# pcb1_24V.net
KiCad netlist of a schematic drawn in EAGLE
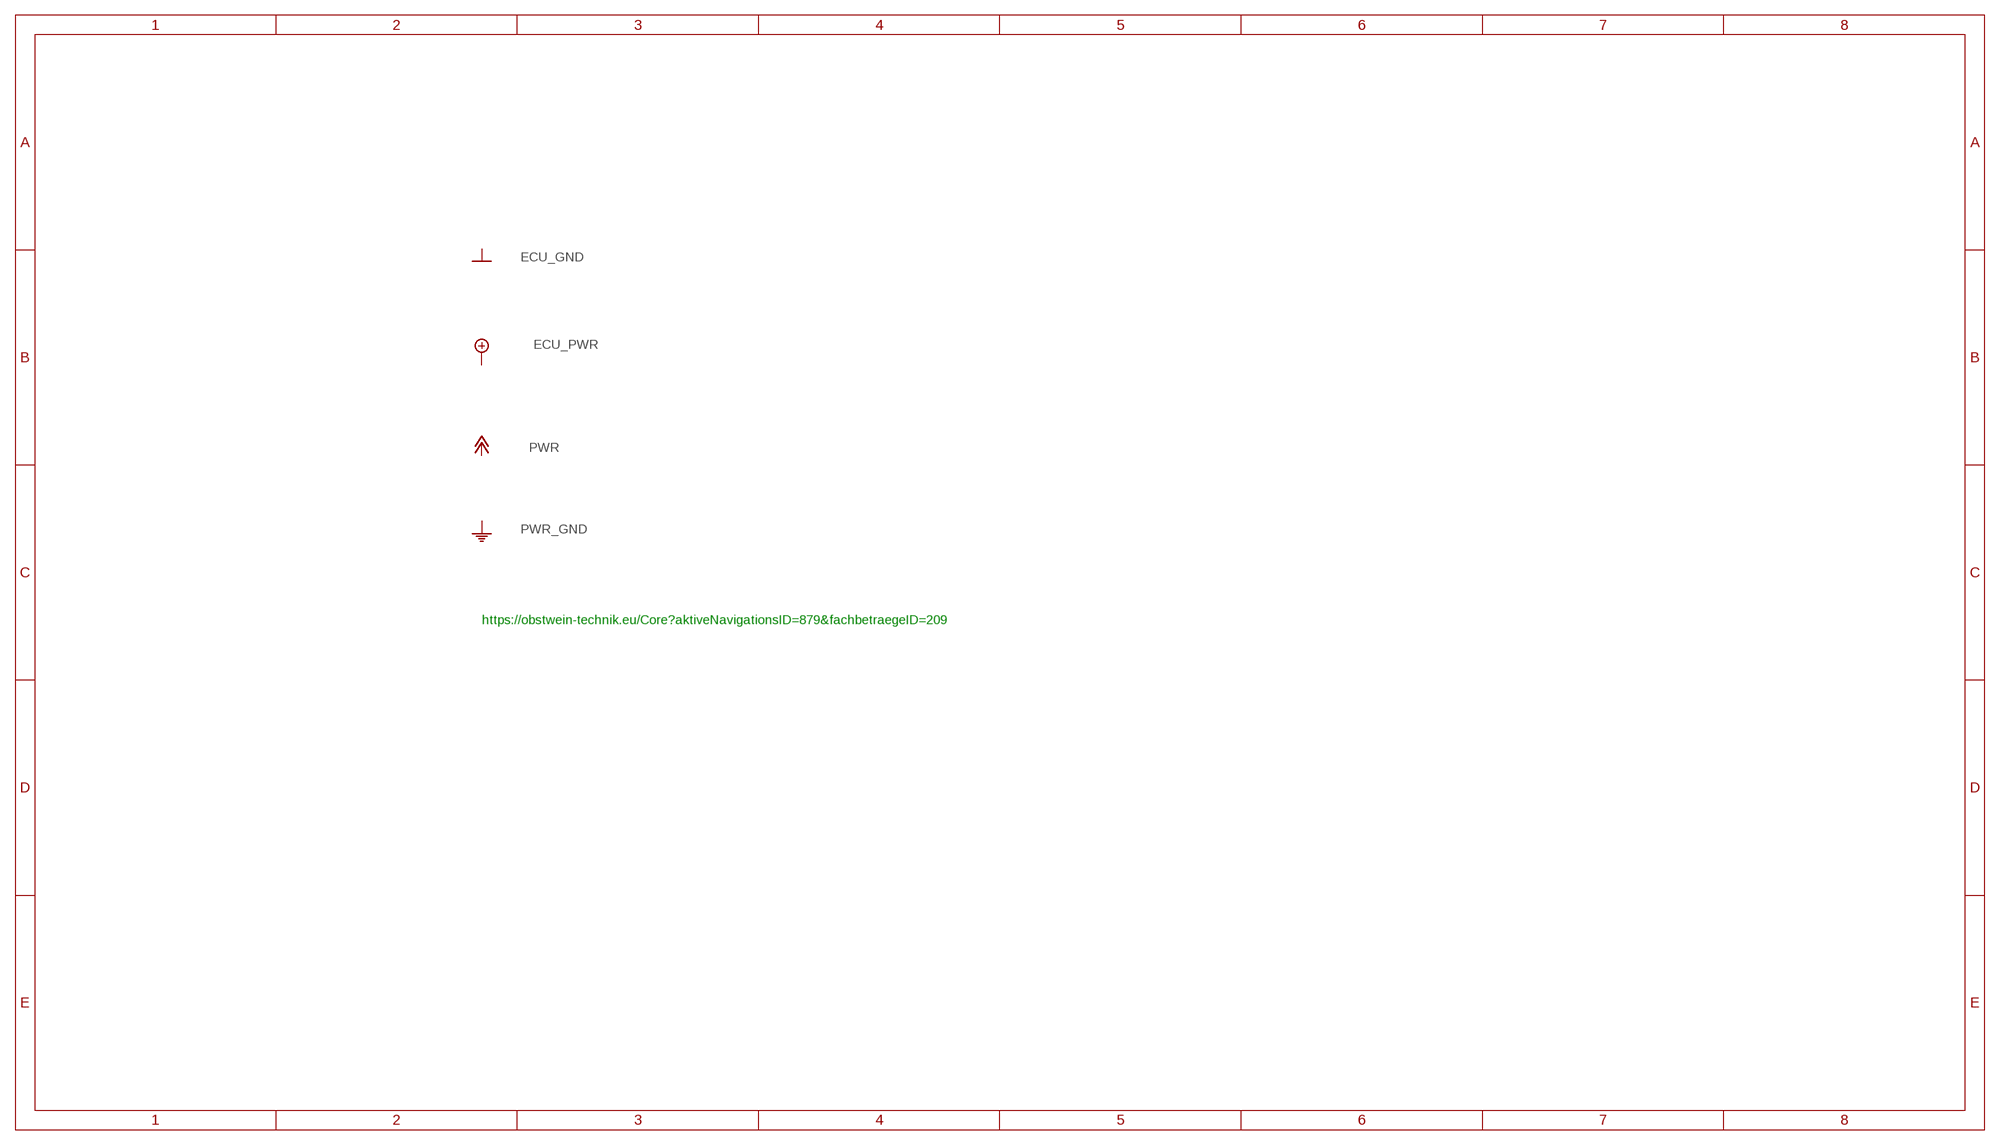
[diagram p0: schematic, sheet 1]
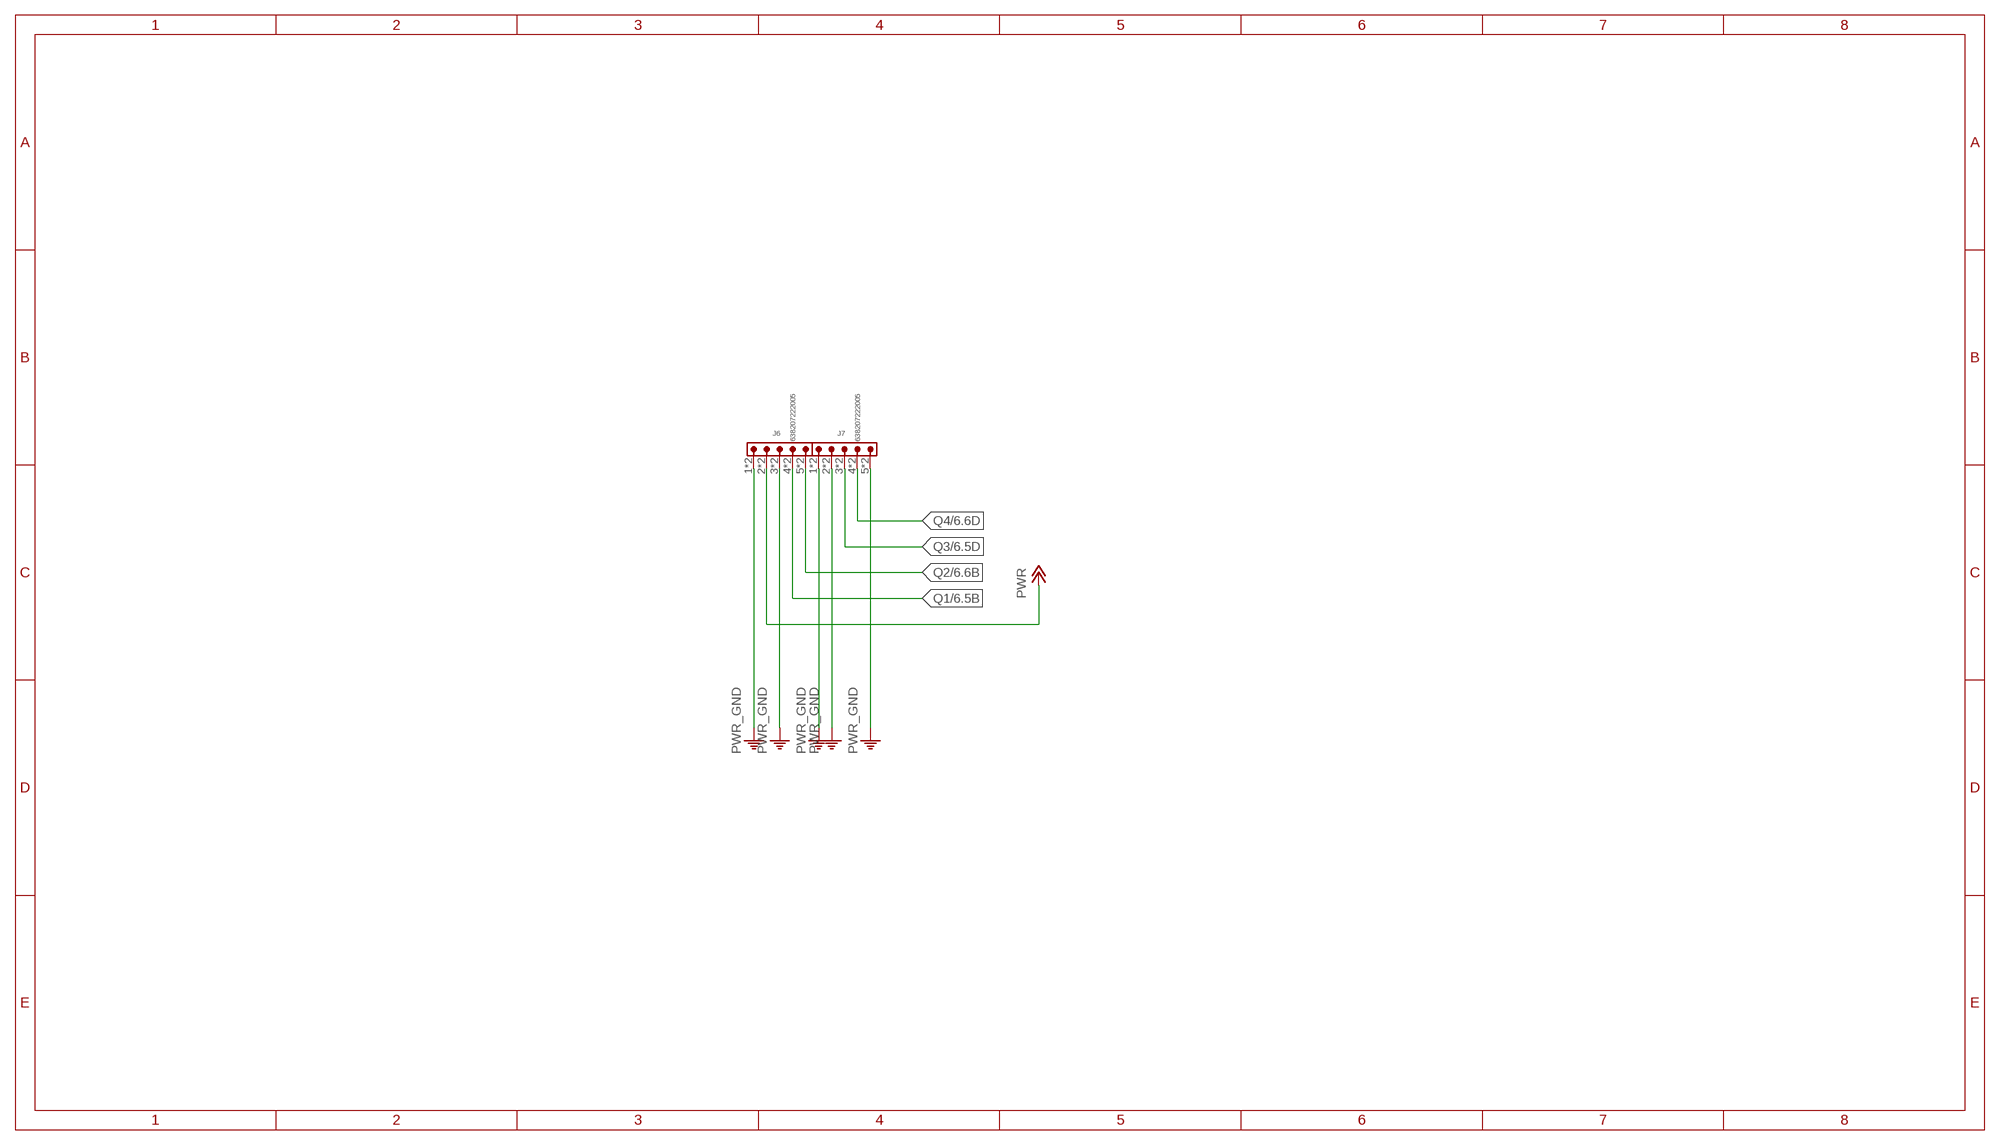
[diagram p1: schematic, sheet 2]
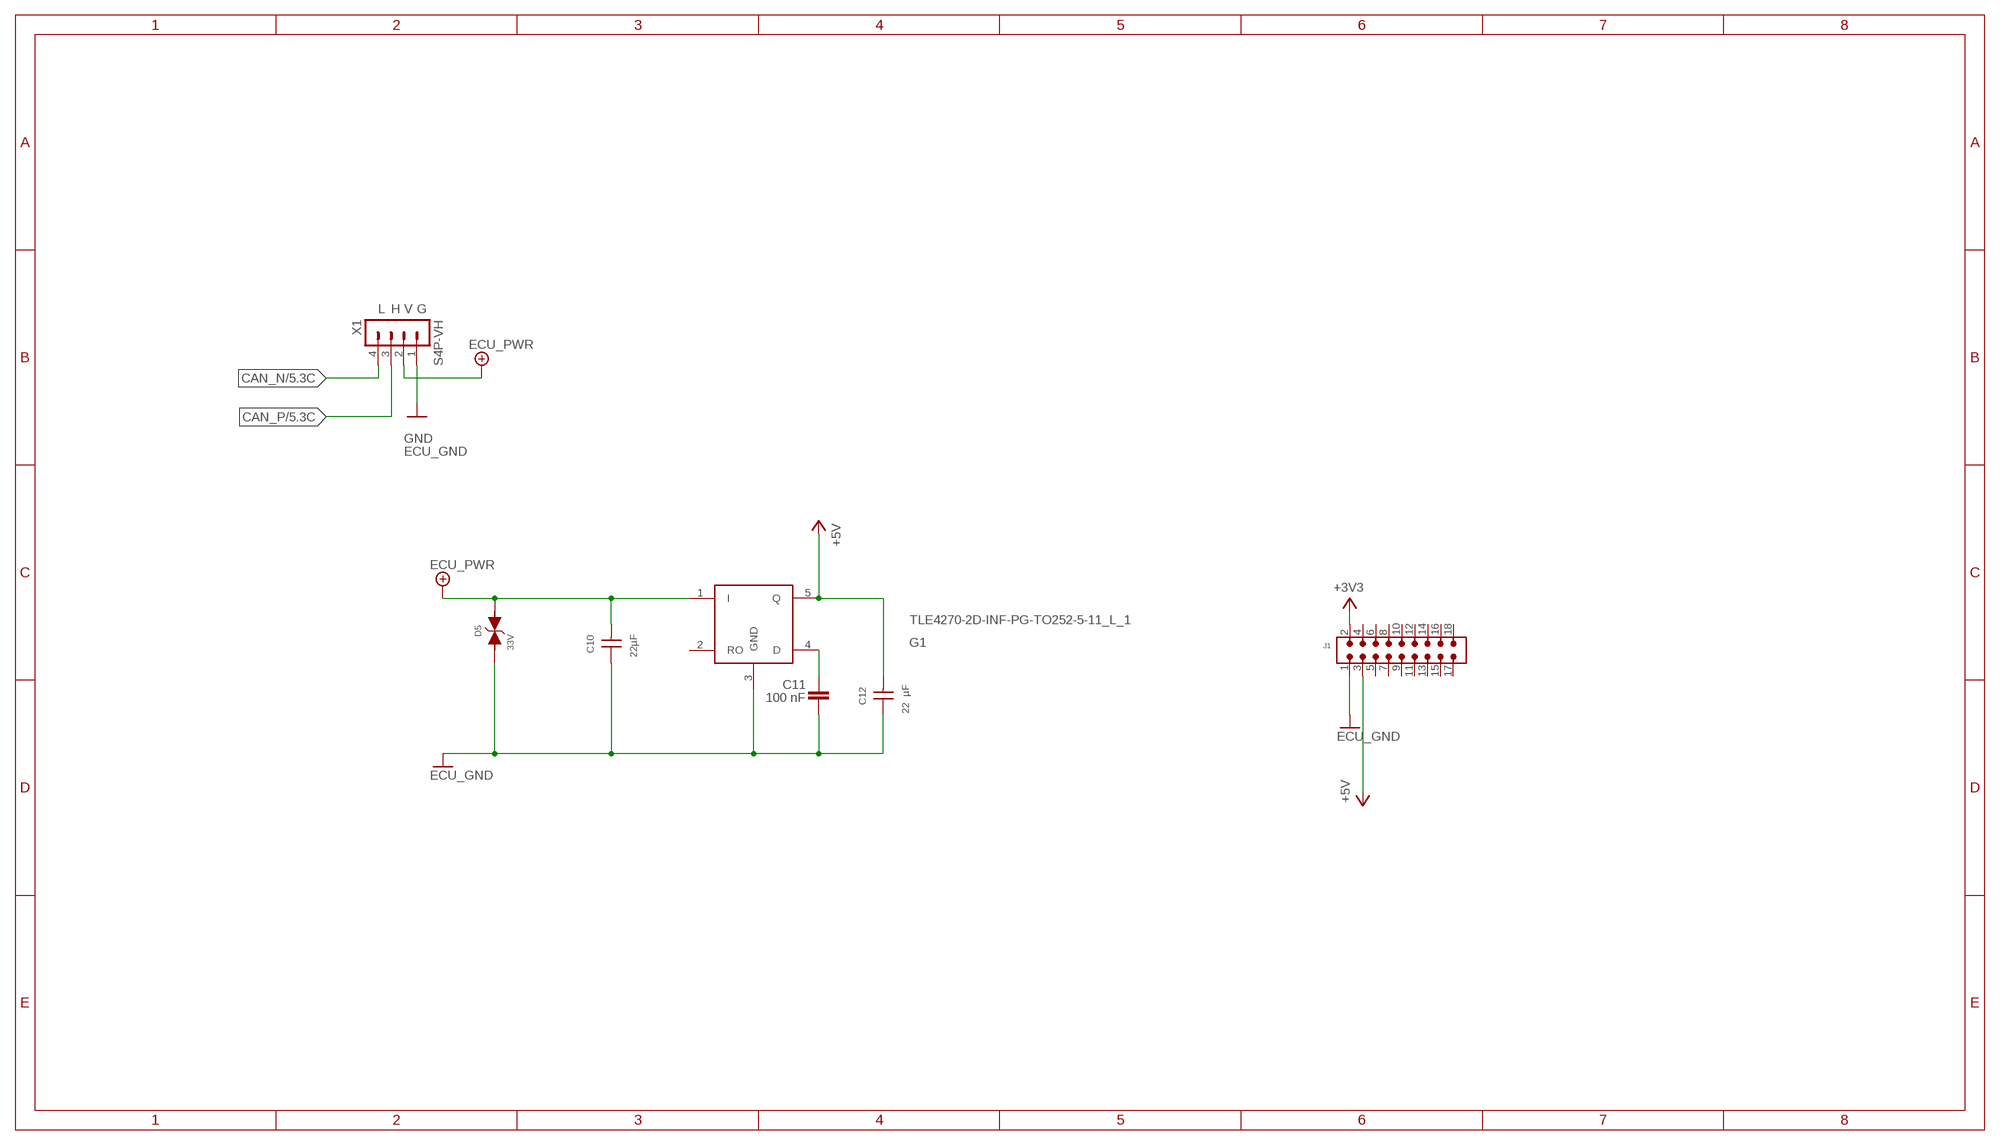
[diagram p2: schematic, sheet 3]
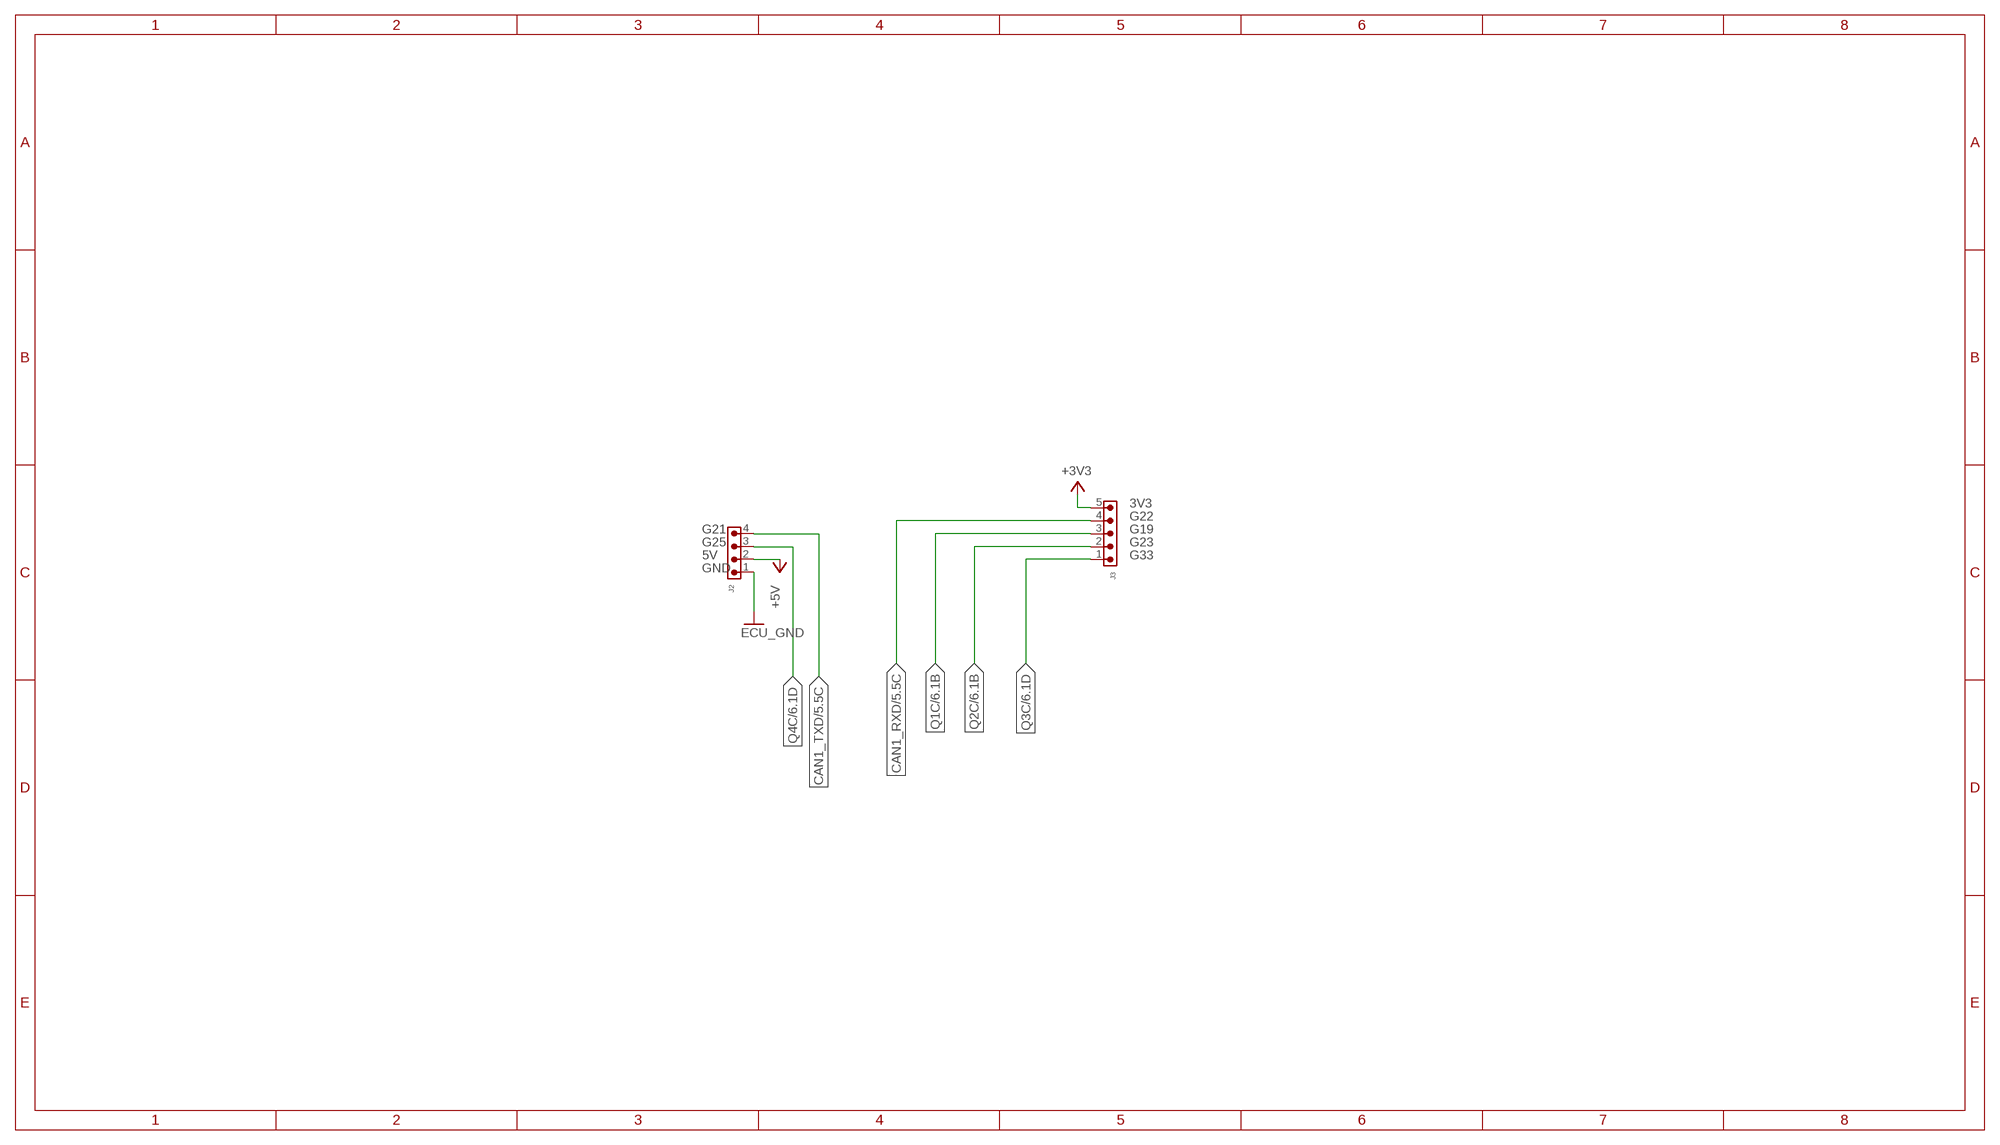
[diagram p3: schematic, sheet 4]
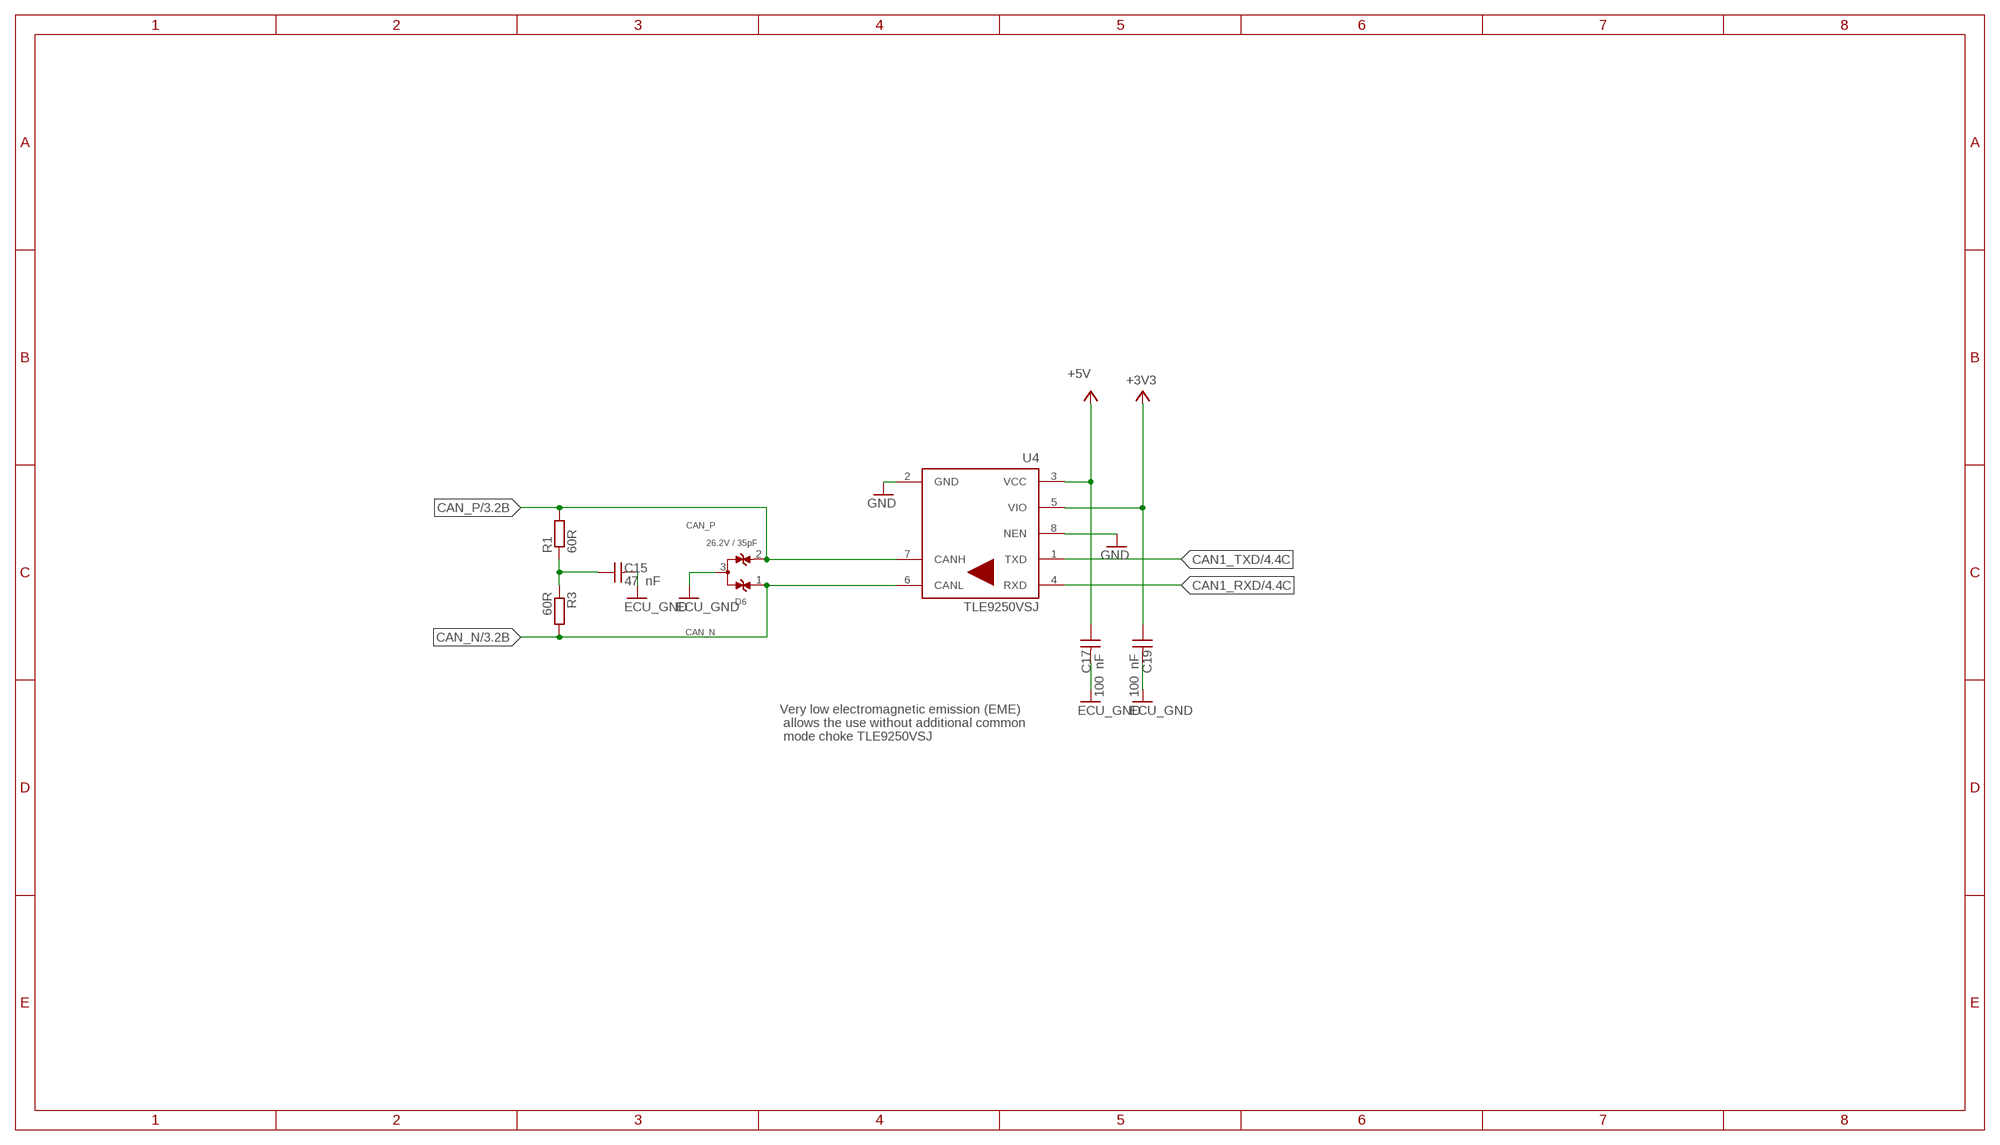
[diagram p4: schematic, sheet 5]
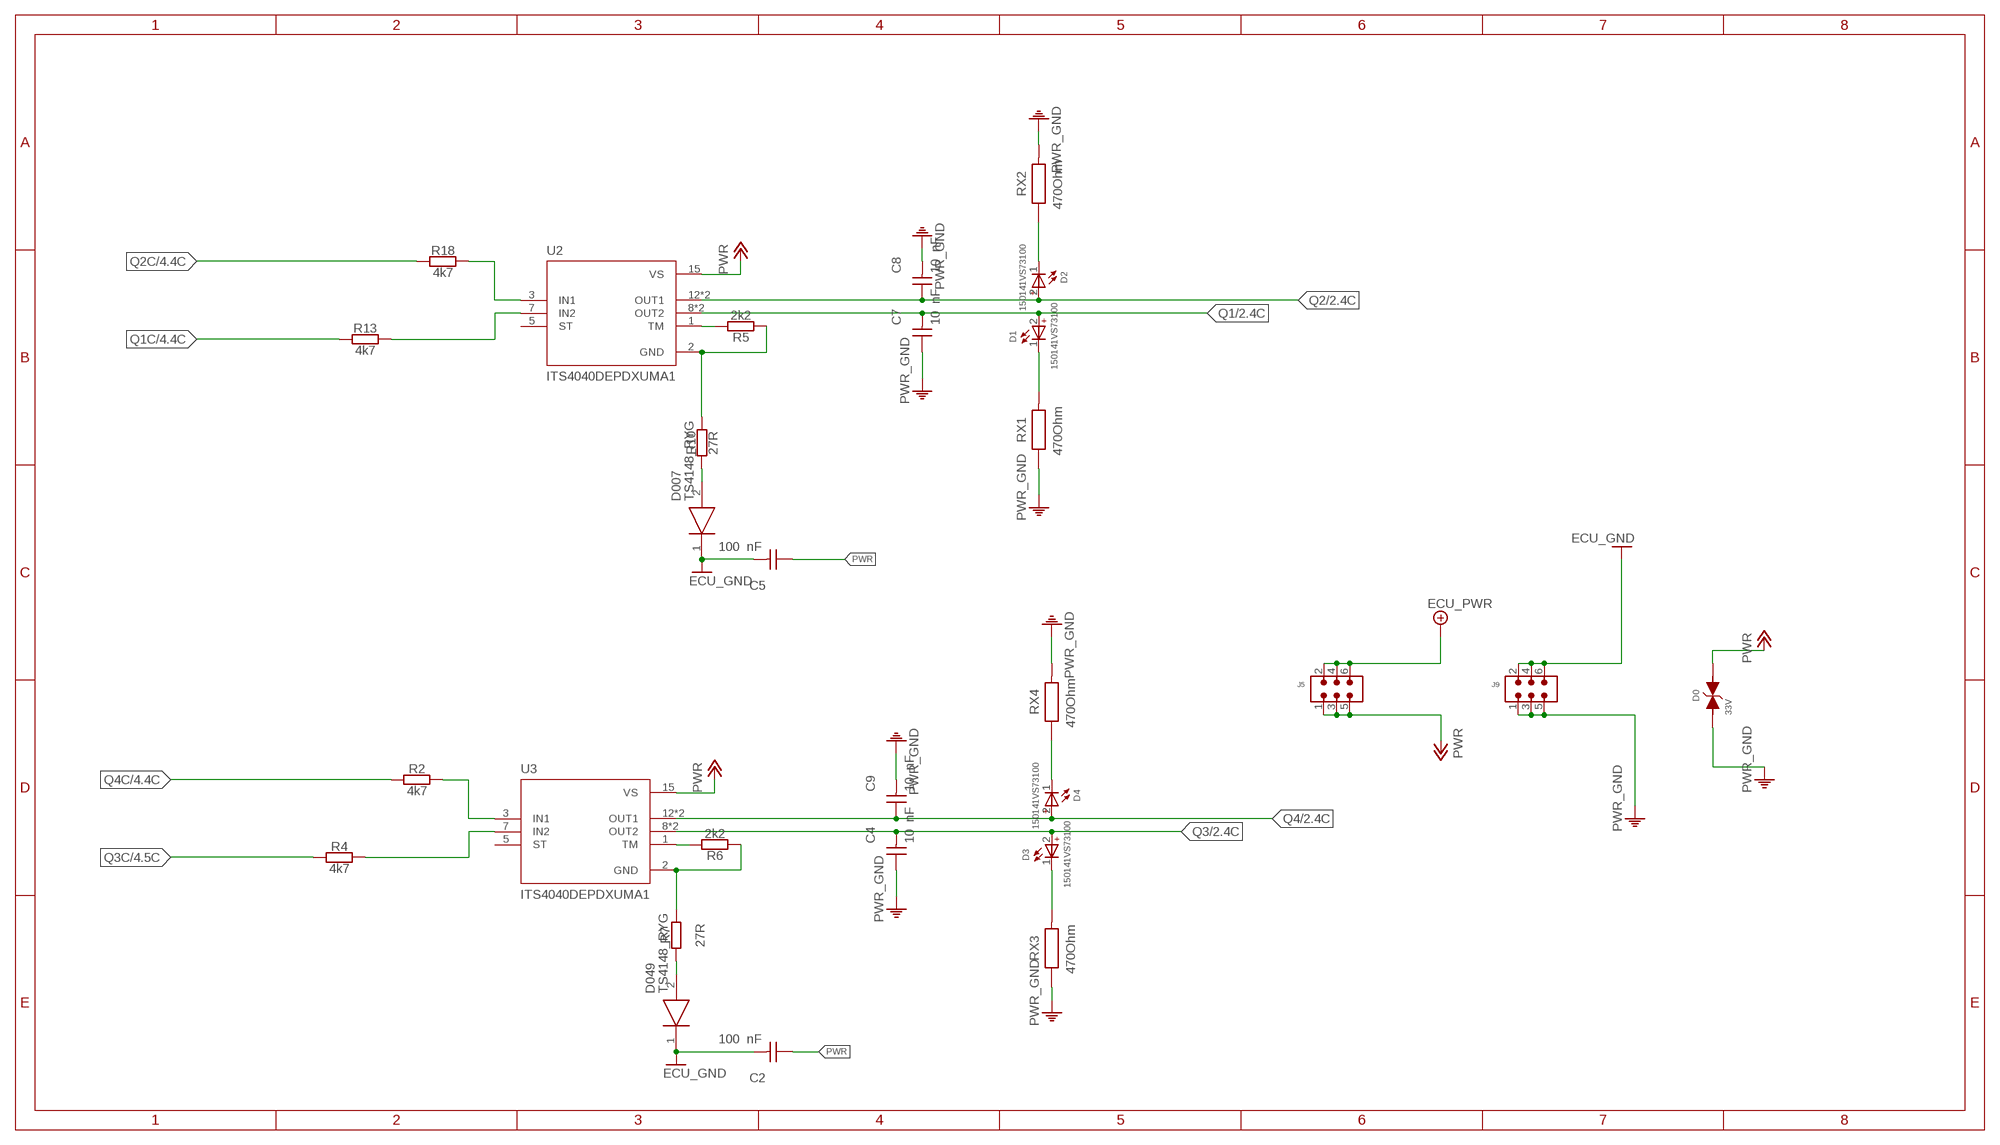
[diagram p5: schematic, sheet 6]

(export (version "E")
  (design (tool "Eeschema 10.0.6"))
  (components
    (comp (ref "J6")
      (value "638207222005")
      (footprint "eagle-import:638207222005")
      (libsource (lib "eagle-import") (part "638207222005"))
    )
    (comp (ref "J7")
      (value "638207222005")
      (footprint "eagle-import:638207222005")
      (libsource (lib "eagle-import") (part "638207222005"))
    )
    (comp (ref "C2")
      (value "100 nF")
      (footprint "eagle-import:WCAP-CSGP_0805_H0.8_R")
      (libsource (lib "eagle-import") (part "WCAP-CSGP_0805_H0.8_50V(DC)_R_885012207098"))
    )
    (comp (ref "C4")
      (value "10 nF")
      (footprint "eagle-import:WCAP-CSGP_0805_H0.8_R")
      (libsource (lib "eagle-import") (part "WCAP-CSGP_0805_H0.8_50V(DC)_R_885012207092"))
    )
    (comp (ref "C5")
      (value "100 nF")
      (footprint "eagle-import:WCAP-CSGP_0805_H0.8_R")
      (libsource (lib "eagle-import") (part "WCAP-CSGP_0805_H0.8_50V(DC)_R_885012207098"))
    )
    (comp (ref "C7")
      (value "10 nF")
      (footprint "eagle-import:WCAP-CSGP_0805_H0.8_R")
      (libsource (lib "eagle-import") (part "WCAP-CSGP_0805_H0.8_50V(DC)_R_885012207092"))
    )
    (comp (ref "C8")
      (value "10 nF")
      (footprint "eagle-import:WCAP-CSGP_0805_H0.8_R")
      (libsource (lib "eagle-import") (part "WCAP-CSGP_0805_H0.8_50V(DC)_R_885012207092"))
    )
    (comp (ref "C9")
      (value "10 nF")
      (footprint "eagle-import:WCAP-CSGP_0805_H0.8_R")
      (libsource (lib "eagle-import") (part "WCAP-CSGP_0805_H0.8_50V(DC)_R_885012207092"))
    )
    (comp (ref "D0")
      (value "33V")
      (footprint "eagle-import:WE-TVSP_DO-214AB_BIDIRECTIONAL")
      (libsource (lib "eagle-import") (part "WE-TVSP_DO-214AB_3000W_BI_824551331"))
    )
    (comp (ref "D1")
      (value "150141VS73100")
      (footprint "eagle-import:WL-SMTW_3528")
      (libsource (lib "eagle-import") (part "WL-SMTW_3528_150141VS73100"))
    )
    (comp (ref "D2")
      (value "150141VS73100")
      (footprint "eagle-import:WL-SMTW_3528")
      (libsource (lib "eagle-import") (part "WL-SMTW_3528_150141VS73100"))
    )
    (comp (ref "D3")
      (value "150141VS73100")
      (footprint "eagle-import:WL-SMTW_3528")
      (libsource (lib "eagle-import") (part "WL-SMTW_3528_150141VS73100"))
    )
    (comp (ref "D4")
      (value "150141VS73100")
      (footprint "eagle-import:WL-SMTW_3528")
      (libsource (lib "eagle-import") (part "WL-SMTW_3528_150141VS73100"))
    )
    (comp (ref "D007")
      (value "TS4148_RYG")
      (footprint "eagle-import:DIOC2012X95N")
      (fields
        (field (name "MANUFACTURER_PART_NUMBER") "TS4148 RYG")
        (field (name "MOUSER_PART_NUMBER") "821-TS4148RYG")
      )
      (libsource (lib "eagle-import") (part "TS4148_RYG"))
    )
    (comp (ref "D049")
      (value "TS4148_RYG")
      (footprint "eagle-import:DIOC2012X95N")
      (fields
        (field (name "MANUFACTURER_PART_NUMBER") "TS4148 RYG")
        (field (name "MOUSER_PART_NUMBER") "821-TS4148RYG")
      )
      (libsource (lib "eagle-import") (part "TS4148_RYG"))
    )
    (comp (ref "J5")
      (value "6130XX21121_61300621121")
      (footprint "eagle-import:61300621121")
      (libsource (lib "eagle-import") (part "6130XX21121_61300621121"))
    )
    (comp (ref "J9")
      (value "6130XX21121_61300621121")
      (footprint "eagle-import:61300621121")
      (libsource (lib "eagle-import") (part "6130XX21121_61300621121"))
    )
    (comp (ref "R2")
      (value "4k7")
      (footprint "eagle-import:R0805")
      (libsource (lib "eagle-import") (part "R-EU_R0805"))
    )
    (comp (ref "R4")
      (value "4k7")
      (footprint "eagle-import:R0805")
      (libsource (lib "eagle-import") (part "R-EU_R0805"))
    )
    (comp (ref "R5")
      (value "2k2")
      (footprint "eagle-import:R0805")
      (libsource (lib "eagle-import") (part "R-EU_R0805"))
    )
    (comp (ref "R6")
      (value "2k2")
      (footprint "eagle-import:R0805")
      (libsource (lib "eagle-import") (part "R-EU_R0805"))
    )
    (comp (ref "R7")
      (value "27R")
      (footprint "eagle-import:R0805")
      (libsource (lib "eagle-import") (part "R-EU_R0805"))
    )
    (comp (ref "R10")
      (value "27R")
      (footprint "eagle-import:R0805")
      (libsource (lib "eagle-import") (part "R-EU_R0805"))
    )
    (comp (ref "R13")
      (value "4k7")
      (footprint "eagle-import:R0805")
      (libsource (lib "eagle-import") (part "R-EU_R0805"))
    )
    (comp (ref "R18")
      (value "4k7")
      (footprint "eagle-import:R0805")
      (libsource (lib "eagle-import") (part "R-EU_R0805"))
    )
    (comp (ref "RX1")
      (value "470Ohm")
      (footprint "eagle-import:WRIS-KWKB_0612")
      (libsource (lib "eagle-import") (part "WRIS-KWKB_0612_561020132023"))
    )
    (comp (ref "RX2")
      (value "470Ohm")
      (footprint "eagle-import:WRIS-KWKB_0612")
      (libsource (lib "eagle-import") (part "WRIS-KWKB_0612_561020132023"))
    )
    (comp (ref "RX3")
      (value "470Ohm")
      (footprint "eagle-import:WRIS-KWKB_0612")
      (libsource (lib "eagle-import") (part "WRIS-KWKB_0612_561020132023"))
    )
    (comp (ref "RX4")
      (value "470Ohm")
      (footprint "eagle-import:WRIS-KWKB_0612")
      (libsource (lib "eagle-import") (part "WRIS-KWKB_0612_561020132023"))
    )
    (comp (ref "U2")
      (value "ITS4040DEPDXUMA1")
      (footprint "eagle-import:SOP65P600X115-15N")
      (fields
        (field (name "DIGI-KEY_PART_NUMBER") "ITS4040DEPDXUMA1TR-ND")
        (field (name "MF") "Infineon Technologies")
      )
      (libsource (lib "eagle-import") (part "ITS4040DEPDXUMA1"))
    )
    (comp (ref "U3")
      (value "ITS4040DEPDXUMA1")
      (footprint "eagle-import:SOP65P600X115-15N")
      (fields
        (field (name "DIGI-KEY_PART_NUMBER") "ITS4040DEPDXUMA1TR-ND")
        (field (name "MF") "Infineon Technologies")
      )
      (libsource (lib "eagle-import") (part "ITS4040DEPDXUMA1"))
    )
    (comp (ref "C15")
      (value "47 nF")
      (footprint "eagle-import:WCAP-CSGP_0805_H0.8_R")
      (libsource (lib "eagle-import") (part "WCAP-CSGP_0805_H0.8_50V(DC)_R_885012207096"))
    )
    (comp (ref "C17")
      (value "100 nF")
      (footprint "eagle-import:WCAP-CSGP_0805_H0.8_R")
      (libsource (lib "eagle-import") (part "WCAP-CSGP_0805_H0.8_50V(DC)_R_885012207098"))
    )
    (comp (ref "C19")
      (value "100 nF")
      (footprint "eagle-import:WCAP-CSGP_0805_H0.8_R")
      (libsource (lib "eagle-import") (part "WCAP-CSGP_0805_H0.8_50V(DC)_R_885012207098"))
    )
    (comp (ref "D6")
      (value "26.2V / 35pF")
      (footprint "eagle-import:WE-TVS_SOT23-3L")
      (libsource (lib "eagle-import") (part "WE-TVS_SOT23-3L_824098024"))
    )
    (comp (ref "R1")
      (value "60R")
      (footprint "eagle-import:R0805")
      (libsource (lib "eagle-import") (part "R-EU_R0805"))
    )
    (comp (ref "R3")
      (value "60R")
      (footprint "eagle-import:R0805")
      (libsource (lib "eagle-import") (part "R-EU_R0805"))
    )
    (comp (ref "U4")
      (value "TLE9250VSJ")
      (footprint "eagle-import:SOIC127P602X173-8N-V")
      (libsource (lib "eagle-import") (part "TLE9250VSJ"))
    )
    (comp (ref "J2")
      (value "6130XX11121_61300411121")
      (footprint "eagle-import:61300411121")
      (libsource (lib "eagle-import") (part "6130XX11121_61300411121"))
    )
    (comp (ref "J3")
      (value "6130XX11121_61300511121")
      (footprint "eagle-import:61300511121")
      (libsource (lib "eagle-import") (part "6130XX11121_61300511121"))
    )
    (comp (ref "C10")
      (value "22µF")
      (footprint "eagle-import:WCAP-CSGP_1210_H2.5")
      (libsource (lib "eagle-import") (part "WCAP-CSGP_1210_H2.5_25V(DC)_885012109014"))
    )
    (comp (ref "C11")
      (value "100 nF")
      (footprint "eagle-import:WCAP-CSGP_0402")
      (libsource (lib "eagle-import") (part "WCAP-CSGP_0402_16V(DC)_885012205037"))
    )
    (comp (ref "C12")
      (value "22 µF")
      (footprint "eagle-import:WCAP-CSGP_0805_H1.25_R")
      (libsource (lib "eagle-import") (part "WCAP-CSGP_0805_H1.25_10V(DC)_885012107011"))
    )
    (comp (ref "D5")
      (value "33V")
      (footprint "eagle-import:WE-TVSP_DO-214AB_BIDIRECTIONAL")
      (libsource (lib "eagle-import") (part "WE-TVSP_DO-214AB_3000W_BI_824551331"))
    )
    (comp (ref "G1")
      (value "TLE4270-2D-INF-PG-TO252-5-11_L_1")
      (footprint "eagle-import:INF-PG-TO252-5-11_L_1PRIMARY")
      (libsource (lib "eagle-import") (part "TLE4270-2D-INF-PG-TO252-5-11_L_1"))
    )
    (comp (ref "J1")
      (value "6130XX21121_61301821121")
      (footprint "eagle-import:61301821121")
      (libsource (lib "eagle-import") (part "6130XX21121_61301821121"))
    )
    (comp (ref "X1")
      (value "S4P-VH")
      (footprint "eagle-import:S4P-VH")
      (libsource (lib "eagle-import") (part "S4P-VH"))
    )
  )
  (nets
    (net (code "1") (name "+3V3") (class "Default")
      (node (ref "C19") (pin "1") (pinfunction "1_1") (pintype "passive"))
      (node (ref "J1") (pin "2") (pinfunction "2_2") (pintype "passive"))
      (node (ref "J3") (pin "5") (pinfunction "5_5") (pintype "passive"))
      (node (ref "U4") (pin "5") (pinfunction "VIO_5") (pintype "input"))
    )
    (net (code "2") (name "+5V") (class "Default")
      (node (ref "C12") (pin "2") (pinfunction "2_2") (pintype "passive"))
      (node (ref "C17") (pin "1") (pinfunction "1_1") (pintype "passive"))
      (node (ref "G1") (pin "5") (pinfunction "Q_5") (pintype "power_in"))
      (node (ref "J1") (pin "3") (pinfunction "3_3") (pintype "passive"))
      (node (ref "J2") (pin "2") (pinfunction "2_2") (pintype "passive"))
      (node (ref "U4") (pin "3") (pinfunction "VCC_3") (pintype "input"))
    )
    (net (code "3") (name "CAN1_RXD") (class "Default")
      (node (ref "J3") (pin "4") (pinfunction "4_4") (pintype "passive"))
      (node (ref "U4") (pin "4") (pinfunction "RXD_4") (pintype "output"))
    )
    (net (code "4") (name "CAN1_TXD") (class "Default")
      (node (ref "J2") (pin "4") (pinfunction "4_4") (pintype "passive"))
      (node (ref "U4") (pin "1") (pinfunction "TXD_1") (pintype "input"))
    )
    (net (code "5") (name "CAN_N") (class "Default")
      (node (ref "D6") (pin "1") (pinfunction "1_1") (pintype "passive"))
      (node (ref "R3") (pin "2") (pinfunction "2_2") (pintype "passive"))
      (node (ref "U4") (pin "6") (pinfunction "CANL_6") (pintype "bidirectional"))
      (node (ref "X1") (pin "4") (pinfunction "4_4") (pintype "passive"))
    )
    (net (code "6") (name "CAN_P") (class "Default")
      (node (ref "D6") (pin "2") (pinfunction "2_2") (pintype "passive"))
      (node (ref "R1") (pin "2") (pinfunction "2_2") (pintype "passive"))
      (node (ref "U4") (pin "7") (pinfunction "CANH_7") (pintype "bidirectional"))
      (node (ref "X1") (pin "3") (pinfunction "3_3") (pintype "passive"))
    )
    (net (code "7") (name "ECU_GND") (class "Default")
      (node (ref "C10") (pin "1") (pinfunction "1_1") (pintype "passive"))
      (node (ref "C11") (pin "2") (pinfunction "2_2") (pintype "passive"))
      (node (ref "C12") (pin "1") (pinfunction "1_1") (pintype "passive"))
      (node (ref "C15") (pin "2") (pinfunction "2_2") (pintype "passive"))
      (node (ref "C17") (pin "2") (pinfunction "2_2") (pintype "passive"))
      (node (ref "C19") (pin "2") (pinfunction "2_2") (pintype "passive"))
      (node (ref "C2") (pin "2") (pinfunction "2_2") (pintype "passive"))
      (node (ref "C5") (pin "2") (pinfunction "2_2") (pintype "passive"))
      (node (ref "D007") (pin "1") (pinfunction "K_1") (pintype "bidirectional"))
      (node (ref "D049") (pin "1") (pinfunction "K_1") (pintype "bidirectional"))
      (node (ref "D5") (pin "1") (pinfunction "1_1") (pintype "passive"))
      (node (ref "D6") (pin "3") (pinfunction "3_3") (pintype "passive"))
      (node (ref "G1") (pin "3") (pinfunction "GND_3") (pintype "power_in"))
      (node (ref "J1") (pin "1") (pinfunction "1_1") (pintype "passive"))
      (node (ref "J2") (pin "1") (pinfunction "1_1") (pintype "passive"))
      (node (ref "J9") (pin "2") (pinfunction "2_2") (pintype "passive"))
      (node (ref "J9") (pin "4") (pinfunction "4_4") (pintype "passive"))
      (node (ref "J9") (pin "6") (pinfunction "6_6") (pintype "passive"))
      (node (ref "U4") (pin "2") (pinfunction "GND_2") (pintype "power_in"))
      (node (ref "U4") (pin "8") (pinfunction "NEN_8") (pintype "input"))
      (node (ref "X1") (pin "1") (pinfunction "1_1") (pintype "passive"))
    )
    (net (code "8") (name "ECU_PWR") (class "Default")
      (node (ref "C10") (pin "2") (pinfunction "2_2") (pintype "passive"))
      (node (ref "D5") (pin "2") (pinfunction "2_2") (pintype "passive"))
      (node (ref "G1") (pin "1") (pinfunction "I_1") (pintype "power_in"))
      (node (ref "J5") (pin "2") (pinfunction "2_2") (pintype "passive"))
      (node (ref "J5") (pin "4") (pinfunction "4_4") (pintype "passive"))
      (node (ref "J5") (pin "6") (pinfunction "6_6") (pintype "passive"))
      (node (ref "X1") (pin "2") (pinfunction "2_2") (pintype "passive"))
    )
    (net (code "9") (name "Net-(C15-Pad1)") (class "Default")
      (node (ref "C15") (pin "1") (pinfunction "1_1") (pintype "passive"))
      (node (ref "R1") (pin "1") (pinfunction "1_1") (pintype "passive"))
      (node (ref "R3") (pin "1") (pinfunction "1_1") (pintype "passive"))
    )
    (net (code "10") (name "Net-(D1--)") (class "Default")
      (node (ref "D1") (pin "1") (pinfunction "-_1") (pintype "passive"))
      (node (ref "RX1") (pin "2") (pinfunction "2_2") (pintype "passive"))
    )
    (net (code "11") (name "Net-(D2--)") (class "Default")
      (node (ref "D2") (pin "1") (pinfunction "-_1") (pintype "passive"))
      (node (ref "RX2") (pin "1") (pinfunction "1_1") (pintype "passive"))
    )
    (net (code "12") (name "Net-(D3--)") (class "Default")
      (node (ref "D3") (pin "1") (pinfunction "-_1") (pintype "passive"))
      (node (ref "RX3") (pin "2") (pinfunction "2_2") (pintype "passive"))
    )
    (net (code "13") (name "Net-(D4--)") (class "Default")
      (node (ref "D4") (pin "1") (pinfunction "-_1") (pintype "passive"))
      (node (ref "RX4") (pin "1") (pinfunction "1_1") (pintype "passive"))
    )
    (net (code "14") (name "Net-(D007-A)") (class "Default")
      (node (ref "D007") (pin "2") (pinfunction "A_2") (pintype "bidirectional"))
      (node (ref "R10") (pin "1") (pinfunction "1_1") (pintype "passive"))
    )
    (net (code "15") (name "Net-(D049-A)") (class "Default")
      (node (ref "D049") (pin "2") (pinfunction "A_2") (pintype "bidirectional"))
      (node (ref "R7") (pin "1") (pinfunction "1_1") (pintype "passive"))
    )
    (net (code "16") (name "Net-(G1-D)") (class "Default")
      (node (ref "C11") (pin "1") (pinfunction "1_1") (pintype "passive"))
      (node (ref "G1") (pin "4") (pinfunction "D_4") (pintype "bidirectional"))
    )
    (net (code "17") (name "Net-(U2-GND)") (class "Default")
      (node (ref "R10") (pin "2") (pinfunction "2_2") (pintype "passive"))
      (node (ref "R5") (pin "1") (pinfunction "1_1") (pintype "passive"))
      (node (ref "U2") (pin "2") (pinfunction "GND_2") (pintype "power_in"))
    )
    (net (code "18") (name "Net-(U2-IN1)") (class "Default")
      (node (ref "R18") (pin "2") (pinfunction "2_2") (pintype "passive"))
      (node (ref "U2") (pin "3") (pinfunction "IN1_3") (pintype "input"))
    )
    (net (code "19") (name "Net-(U2-IN2)") (class "Default")
      (node (ref "R13") (pin "2") (pinfunction "2_2") (pintype "passive"))
      (node (ref "U2") (pin "7") (pinfunction "IN2_7") (pintype "input"))
    )
    (net (code "20") (name "Net-(U2-TM)") (class "Default")
      (node (ref "R5") (pin "2") (pinfunction "2_2") (pintype "passive"))
      (node (ref "U2") (pin "1") (pinfunction "TM_1") (pintype "passive"))
    )
    (net (code "21") (name "Net-(U3-GND)") (class "Default")
      (node (ref "R6") (pin "1") (pinfunction "1_1") (pintype "passive"))
      (node (ref "R7") (pin "2") (pinfunction "2_2") (pintype "passive"))
      (node (ref "U3") (pin "2") (pinfunction "GND_2") (pintype "power_in"))
    )
    (net (code "22") (name "Net-(U3-IN1)") (class "Default")
      (node (ref "R2") (pin "2") (pinfunction "2_2") (pintype "passive"))
      (node (ref "U3") (pin "3") (pinfunction "IN1_3") (pintype "input"))
    )
    (net (code "23") (name "Net-(U3-IN2)") (class "Default")
      (node (ref "R4") (pin "2") (pinfunction "2_2") (pintype "passive"))
      (node (ref "U3") (pin "7") (pinfunction "IN2_7") (pintype "input"))
    )
    (net (code "24") (name "Net-(U3-TM)") (class "Default")
      (node (ref "R6") (pin "2") (pinfunction "2_2") (pintype "passive"))
      (node (ref "U3") (pin "1") (pinfunction "TM_1") (pintype "passive"))
    )
    (net (code "25") (name "PWR") (class "Default")
      (node (ref "C2") (pin "1") (pinfunction "1_1") (pintype "passive"))
      (node (ref "C5") (pin "1") (pinfunction "1_1") (pintype "passive"))
      (node (ref "D0") (pin "2") (pinfunction "2_2") (pintype "passive"))
      (node (ref "J5") (pin "1") (pinfunction "1_1") (pintype "passive"))
      (node (ref "J5") (pin "3") (pinfunction "3_3") (pintype "passive"))
      (node (ref "J5") (pin "5") (pinfunction "5_5") (pintype "passive"))
      (node (ref "J6") (pin "2") (pinfunction "2_2") (pintype "passive"))
      (node (ref "J6") (pin "A2") (pinfunction "2_A2") (pintype "passive"))
      (node (ref "U2") (pin "15") (pinfunction "VS_15") (pintype "power_in"))
      (node (ref "U3") (pin "15") (pinfunction "VS_15") (pintype "power_in"))
    )
    (net (code "26") (name "PWR_GND") (class "Default")
      (node (ref "C4") (pin "1") (pinfunction "1_1") (pintype "passive"))
      (node (ref "C7") (pin "1") (pinfunction "1_1") (pintype "passive"))
      (node (ref "C8") (pin "2") (pinfunction "2_2") (pintype "passive"))
      (node (ref "C9") (pin "2") (pinfunction "2_2") (pintype "passive"))
      (node (ref "D0") (pin "1") (pinfunction "1_1") (pintype "passive"))
      (node (ref "J6") (pin "1") (pinfunction "1_1") (pintype "passive"))
      (node (ref "J6") (pin "3") (pinfunction "3_3") (pintype "passive"))
      (node (ref "J6") (pin "A1") (pinfunction "1_A1") (pintype "passive"))
      (node (ref "J6") (pin "A3") (pinfunction "3_A3") (pintype "passive"))
      (node (ref "J7") (pin "1") (pinfunction "1_1") (pintype "passive"))
      (node (ref "J7") (pin "2") (pinfunction "2_2") (pintype "passive"))
      (node (ref "J7") (pin "5") (pinfunction "5_5") (pintype "passive"))
      (node (ref "J7") (pin "A1") (pinfunction "1_A1") (pintype "passive"))
      (node (ref "J7") (pin "A2") (pinfunction "2_A2") (pintype "passive"))
      (node (ref "J7") (pin "A5") (pinfunction "5_A5") (pintype "passive"))
      (node (ref "J9") (pin "1") (pinfunction "1_1") (pintype "passive"))
      (node (ref "J9") (pin "3") (pinfunction "3_3") (pintype "passive"))
      (node (ref "J9") (pin "5") (pinfunction "5_5") (pintype "passive"))
      (node (ref "RX1") (pin "1") (pinfunction "1_1") (pintype "passive"))
      (node (ref "RX2") (pin "2") (pinfunction "2_2") (pintype "passive"))
      (node (ref "RX3") (pin "1") (pinfunction "1_1") (pintype "passive"))
      (node (ref "RX4") (pin "2") (pinfunction "2_2") (pintype "passive"))
    )
    (net (code "27") (name "Q1") (class "Default")
      (node (ref "C7") (pin "2") (pinfunction "2_2") (pintype "passive"))
      (node (ref "D1") (pin "2") (pinfunction "+_2") (pintype "passive"))
      (node (ref "J6") (pin "4") (pinfunction "4_4") (pintype "passive"))
      (node (ref "J6") (pin "A4") (pinfunction "4_A4") (pintype "passive"))
      (node (ref "U2") (pin "10") (pinfunction "OUT2_10") (pintype "output"))
      (node (ref "U2") (pin "8") (pinfunction "OUT2_8") (pintype "output"))
    )
    (net (code "28") (name "Q1C") (class "Default")
      (node (ref "J3") (pin "3") (pinfunction "3_3") (pintype "passive"))
      (node (ref "R13") (pin "1") (pinfunction "1_1") (pintype "passive"))
    )
    (net (code "29") (name "Q2") (class "Default")
      (node (ref "C8") (pin "1") (pinfunction "1_1") (pintype "passive"))
      (node (ref "D2") (pin "2") (pinfunction "+_2") (pintype "passive"))
      (node (ref "J6") (pin "5") (pinfunction "5_5") (pintype "passive"))
      (node (ref "J6") (pin "A5") (pinfunction "5_A5") (pintype "passive"))
      (node (ref "U2") (pin "12") (pinfunction "OUT1_12") (pintype "output"))
      (node (ref "U2") (pin "14") (pinfunction "OUT1_14") (pintype "output"))
    )
    (net (code "30") (name "Q2C") (class "Default")
      (node (ref "J3") (pin "2") (pinfunction "2_2") (pintype "passive"))
      (node (ref "R18") (pin "1") (pinfunction "1_1") (pintype "passive"))
    )
    (net (code "31") (name "Q3") (class "Default")
      (node (ref "C4") (pin "2") (pinfunction "2_2") (pintype "passive"))
      (node (ref "D3") (pin "2") (pinfunction "+_2") (pintype "passive"))
      (node (ref "J7") (pin "3") (pinfunction "3_3") (pintype "passive"))
      (node (ref "J7") (pin "A3") (pinfunction "3_A3") (pintype "passive"))
      (node (ref "U3") (pin "10") (pinfunction "OUT2_10") (pintype "output"))
      (node (ref "U3") (pin "8") (pinfunction "OUT2_8") (pintype "output"))
    )
    (net (code "32") (name "Q3C") (class "Default")
      (node (ref "J3") (pin "1") (pinfunction "1_1") (pintype "passive"))
      (node (ref "R4") (pin "1") (pinfunction "1_1") (pintype "passive"))
    )
    (net (code "33") (name "Q4") (class "Default")
      (node (ref "C9") (pin "1") (pinfunction "1_1") (pintype "passive"))
      (node (ref "D4") (pin "2") (pinfunction "+_2") (pintype "passive"))
      (node (ref "J7") (pin "4") (pinfunction "4_4") (pintype "passive"))
      (node (ref "J7") (pin "A4") (pinfunction "4_A4") (pintype "passive"))
      (node (ref "U3") (pin "12") (pinfunction "OUT1_12") (pintype "output"))
      (node (ref "U3") (pin "14") (pinfunction "OUT1_14") (pintype "output"))
    )
    (net (code "34") (name "Q4C") (class "Default")
      (node (ref "J2") (pin "3") (pinfunction "3_3") (pintype "passive"))
      (node (ref "R2") (pin "1") (pinfunction "1_1") (pintype "passive"))
    )
    (net (code "35") (name "unconnected-(G1-RO-Pad2)") (class "Default")
      (node (ref "G1") (pin "2") (pinfunction "RO_2") (pintype "output"))
    )
    (net (code "36") (name "unconnected-(J1-Pad4)") (class "Default")
      (node (ref "J1") (pin "4") (pinfunction "4_4") (pintype "passive"))
    )
    (net (code "37") (name "unconnected-(J1-Pad5)") (class "Default")
      (node (ref "J1") (pin "5") (pinfunction "5_5") (pintype "passive"))
    )
    (net (code "38") (name "unconnected-(J1-Pad6)") (class "Default")
      (node (ref "J1") (pin "6") (pinfunction "6_6") (pintype "passive"))
    )
    (net (code "39") (name "unconnected-(J1-Pad7)") (class "Default")
      (node (ref "J1") (pin "7") (pinfunction "7_7") (pintype "passive"))
    )
    (net (code "40") (name "unconnected-(J1-Pad8)") (class "Default")
      (node (ref "J1") (pin "8") (pinfunction "8_8") (pintype "passive"))
    )
    (net (code "41") (name "unconnected-(J1-Pad9)") (class "Default")
      (node (ref "J1") (pin "9") (pinfunction "9_9") (pintype "passive"))
    )
    (net (code "42") (name "unconnected-(J1-Pad10)") (class "Default")
      (node (ref "J1") (pin "10") (pinfunction "10_10") (pintype "passive"))
    )
    (net (code "43") (name "unconnected-(J1-Pad11)") (class "Default")
      (node (ref "J1") (pin "11") (pinfunction "11_11") (pintype "passive"))
    )
    (net (code "44") (name "unconnected-(J1-Pad12)") (class "Default")
      (node (ref "J1") (pin "12") (pinfunction "12_12") (pintype "passive"))
    )
    (net (code "45") (name "unconnected-(J1-Pad13)") (class "Default")
      (node (ref "J1") (pin "13") (pinfunction "13_13") (pintype "passive"))
    )
    (net (code "46") (name "unconnected-(J1-Pad14)") (class "Default")
      (node (ref "J1") (pin "14") (pinfunction "14_14") (pintype "passive"))
    )
    (net (code "47") (name "unconnected-(J1-Pad15)") (class "Default")
      (node (ref "J1") (pin "15") (pinfunction "15_15") (pintype "passive"))
    )
    (net (code "48") (name "unconnected-(J1-Pad16)") (class "Default")
      (node (ref "J1") (pin "16") (pinfunction "16_16") (pintype "passive"))
    )
    (net (code "49") (name "unconnected-(J1-Pad17)") (class "Default")
      (node (ref "J1") (pin "17") (pinfunction "17_17") (pintype "passive"))
    )
    (net (code "50") (name "unconnected-(J1-Pad18)") (class "Default")
      (node (ref "J1") (pin "18") (pinfunction "18_18") (pintype "passive"))
    )
    (net (code "51") (name "unconnected-(U2-ST-Pad5)") (class "Default")
      (node (ref "U2") (pin "5") (pinfunction "ST_5") (pintype "input"))
    )
    (net (code "52") (name "unconnected-(U3-ST-Pad5)") (class "Default")
      (node (ref "U3") (pin "5") (pinfunction "ST_5") (pintype "input"))
    )
  )
)
